# module.net
KiCad netlist of a schematic drawn in EAGLE
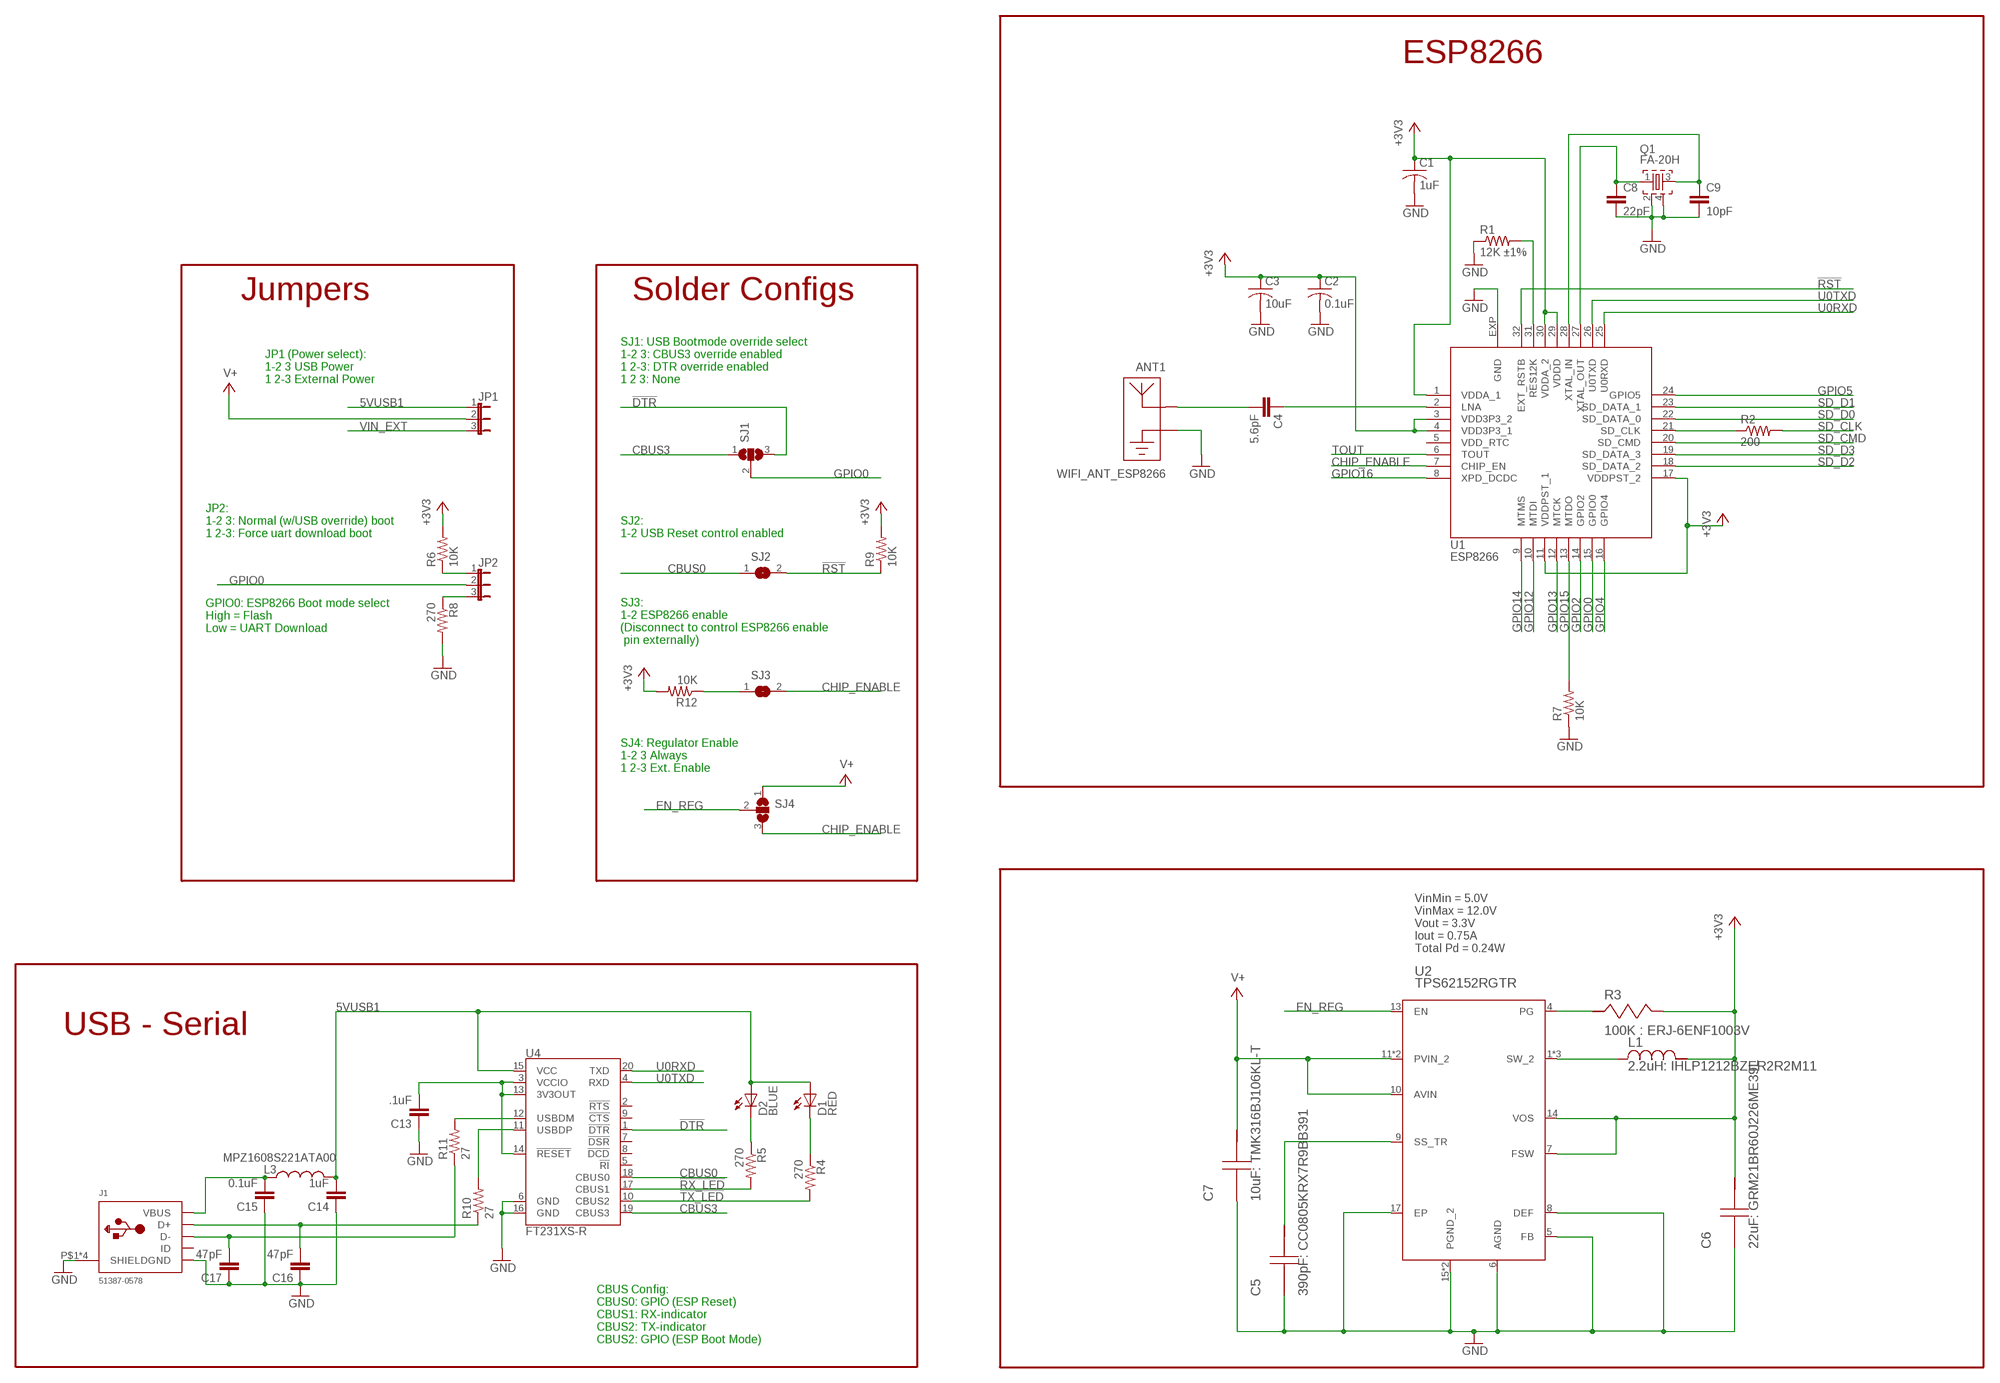
[diagram p0: schematic, sheet 1, part 1 of 2]
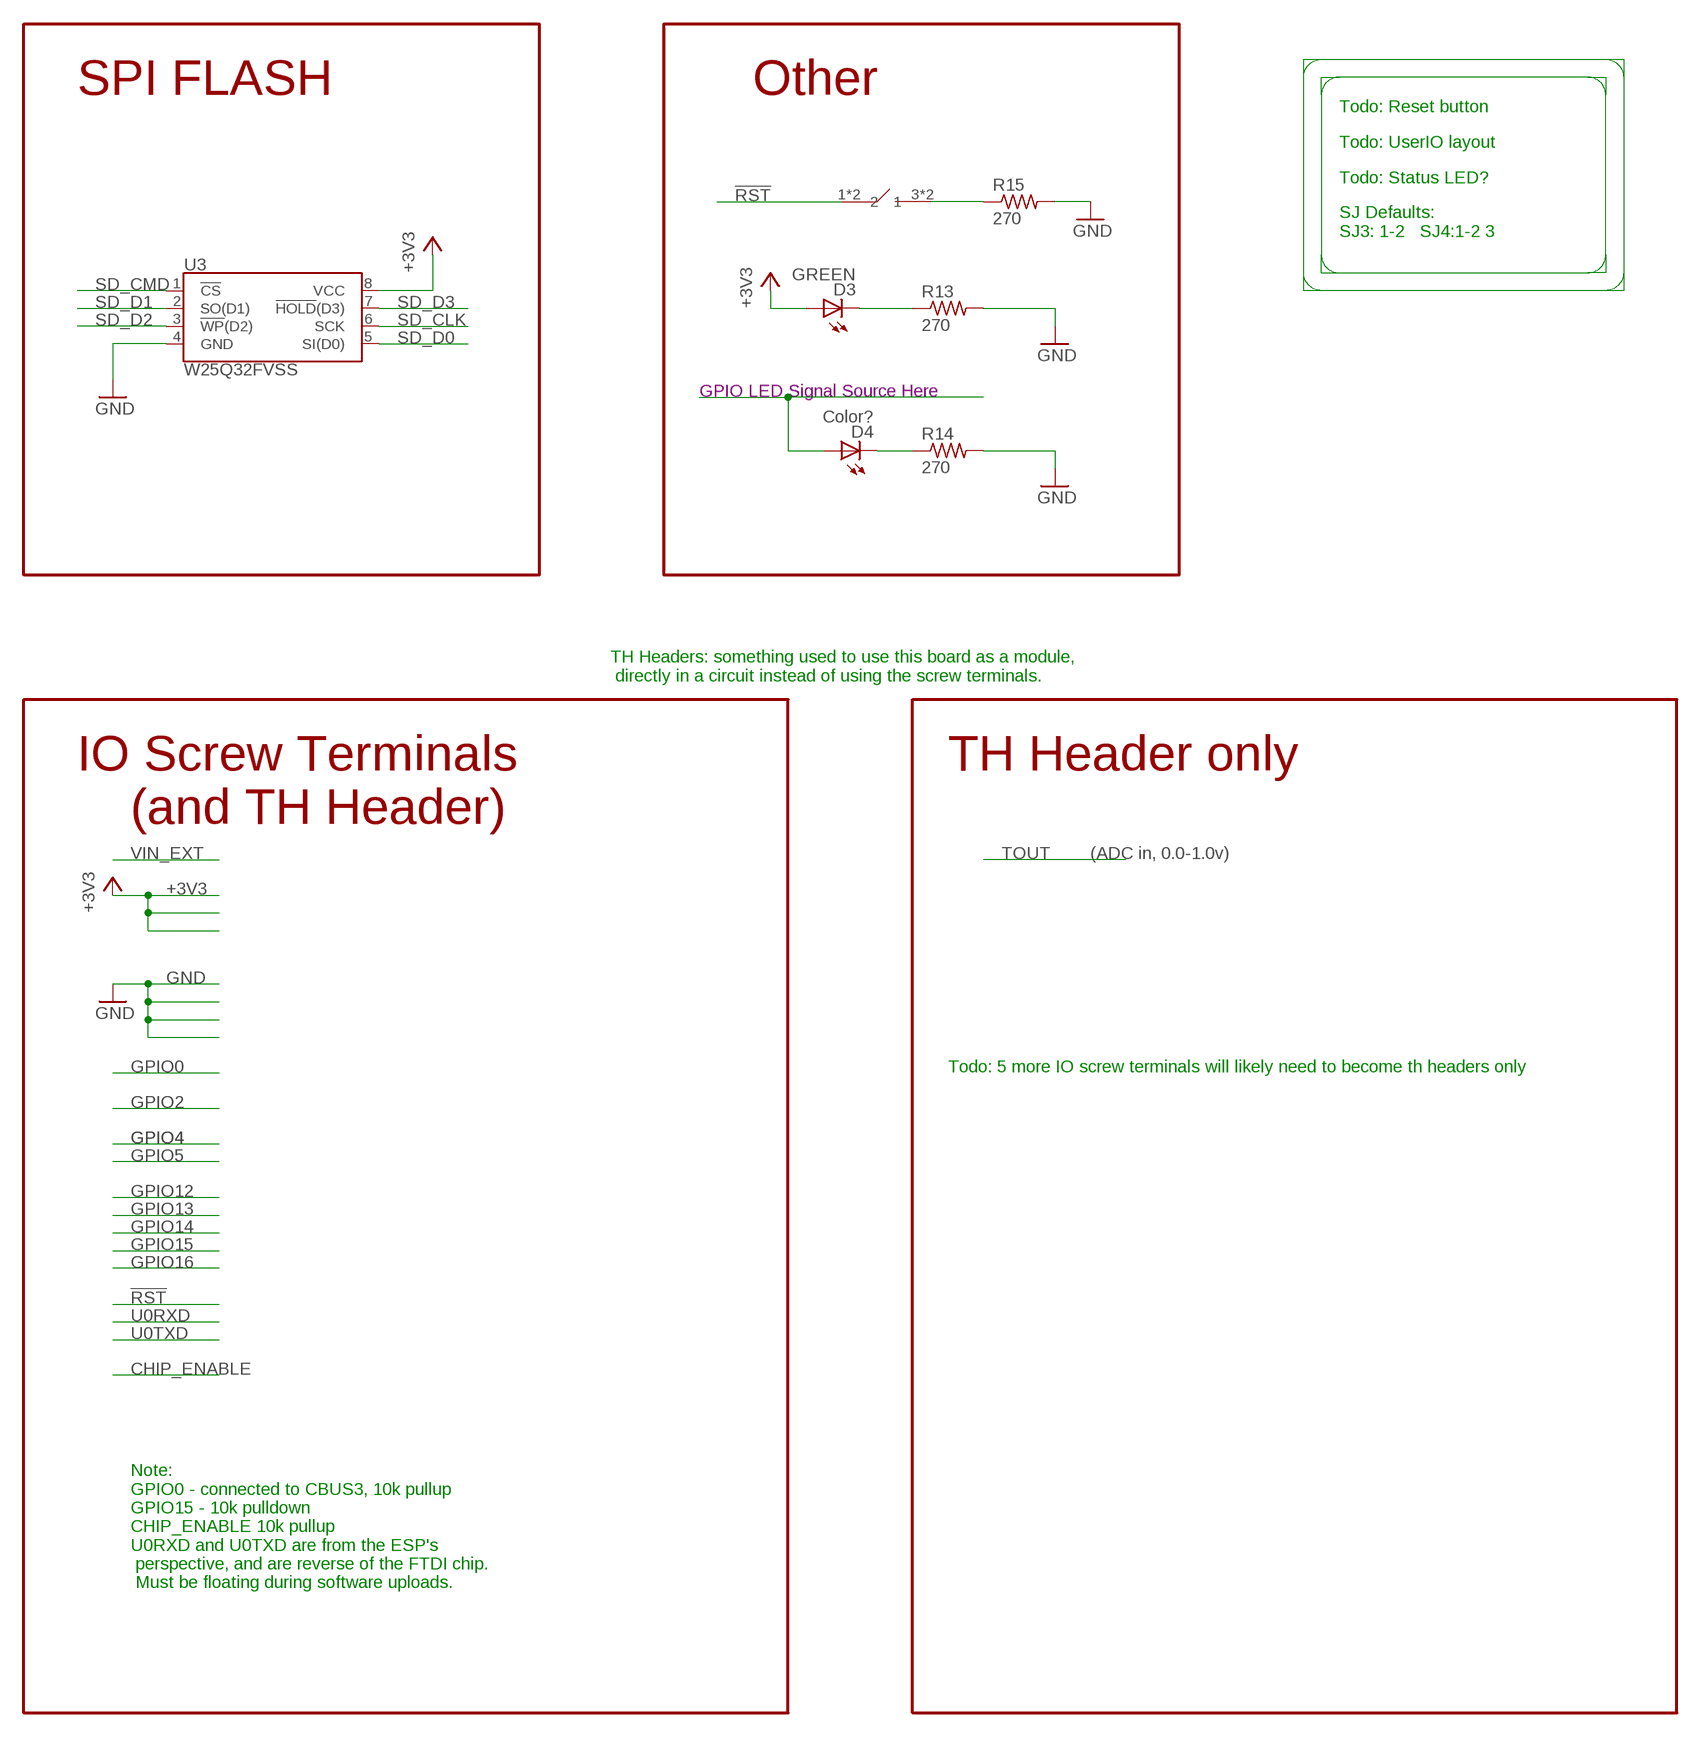
[diagram p1: schematic, sheet 1, part 2 of 2]

(export (version "E")
  (design (tool "Eeschema 10.0.6"))
  (components
    (comp (ref "ANT1")
      (value "WIFI_ANT_ESP8266")
      (footprint "eagle-import:ESP8266_ANT")
      (libsource (lib "eagle-import") (part "WIFI_ANT_ESP8266"))
    )
    (comp (ref "C1")
      (value "1uF")
      (footprint "eagle-import:C0603")
      (libsource (lib "eagle-import") (part "C-USC0603"))
    )
    (comp (ref "C2")
      (value "0.1uF")
      (footprint "eagle-import:C0603")
      (libsource (lib "eagle-import") (part "C-USC0603"))
    )
    (comp (ref "C3")
      (value "10uF")
      (footprint "eagle-import:C0805")
      (libsource (lib "eagle-import") (part "C-USC0805"))
    )
    (comp (ref "C4")
      (value "5.6pF")
      (footprint "eagle-import:C0603")
      (libsource (lib "eagle-import") (part "C-EUC0603"))
    )
    (comp (ref "C5")
      (value "390pF: CC0805KRX7R9BB391")
      (footprint "eagle-import:0805")
      (fields (field (name "MANUFACTURER_PART_NUMBER") "CC0805KRX7R9BB391"))
      (libsource (lib "eagle-import") (part "CC0805KRX7R9BB391"))
    )
    (comp (ref "C6")
      (value "22uF: GRM21BR60J226ME39L")
      (footprint "eagle-import:0805")
      (fields (field (name "MANUFACTURER_PART_NUMBER") "GRM21BR60J226ME39L"))
      (libsource (lib "eagle-import") (part "GRM21BR60J226ME39L"))
    )
    (comp (ref "C7")
      (value "10uF: TMK316BJ106KL-T")
      (footprint "eagle-import:1206")
      (fields (field (name "MANUFACTURER_PART_NUMBER") "TMK316BJ106KL-T"))
      (libsource (lib "eagle-import") (part "TMK316BJ106KL-T"))
    )
    (comp (ref "C8")
      (value "22pF")
      (footprint "eagle-import:C0603")
      (libsource (lib "eagle-import") (part "C-EUC0603"))
    )
    (comp (ref "C9")
      (value "10pF")
      (footprint "eagle-import:C0603")
      (libsource (lib "eagle-import") (part "C-EUC0603"))
    )
    (comp (ref "C13")
      (value ".1uF")
      (footprint "eagle-import:C0603K")
      (libsource (lib "eagle-import") (part "resistor_C-EUC0603K"))
    )
    (comp (ref "C14")
      (value "1uF")
      (footprint "eagle-import:C0603K")
      (libsource (lib "eagle-import") (part "resistor_C-EUC0603K"))
    )
    (comp (ref "C15")
      (value "0.1uF")
      (footprint "eagle-import:C0603K")
      (libsource (lib "eagle-import") (part "resistor_C-EUC0603K"))
    )
    (comp (ref "C16")
      (value "47pF")
      (footprint "eagle-import:C0603K")
      (libsource (lib "eagle-import") (part "resistor_C-EUC0603K"))
    )
    (comp (ref "C17")
      (value "47pF")
      (footprint "eagle-import:C0603K")
      (libsource (lib "eagle-import") (part "resistor_C-EUC0603K"))
    )
    (comp (ref "D1")
      (value "RED")
      (footprint "eagle-import:CHIPLED_0603")
      (libsource (lib "eagle-import") (part "LEDCHIPLED_0603"))
    )
    (comp (ref "D2")
      (value "BLUE")
      (footprint "eagle-import:CHIPLED_0603")
      (libsource (lib "eagle-import") (part "LEDCHIPLED_0603"))
    )
    (comp (ref "D3")
      (value "GREEN")
      (footprint "eagle-import:CHIPLED_0603")
      (libsource (lib "eagle-import") (part "LEDCHIPLED_0603"))
    )
    (comp (ref "D4")
      (value "Color?")
      (footprint "eagle-import:CHIPLED_0603")
      (libsource (lib "eagle-import") (part "LEDCHIPLED_0603"))
    )
    (comp (ref "J1")
      (value "51387-0578")
      (footprint "eagle-import:USB-MINIB-0513870578")
      (libsource (lib "eagle-import") (part "USB"))
    )
    (comp (ref "JP1")
      (value "JP2E")
      (footprint "eagle-import:JP2")
      (libsource (lib "eagle-import") (part "JP2E"))
    )
    (comp (ref "JP2")
      (value "JP2E")
      (footprint "eagle-import:JP2")
      (libsource (lib "eagle-import") (part "JP2E"))
    )
    (comp (ref "L1")
      (value "2.2uH: IHLP1212BZER2R2M11")
      (footprint "eagle-import:IHLP-1212BZ")
      (fields
        (field (name "MANUFACTURER") "Vishay")
        (field (name "MANUFACTURER_PART_NUMBER") "IHLP1212BZER2R2M11")
      )
      (libsource (lib "eagle-import") (part "IHLP1212BZER2R2M11"))
    )
    (comp (ref "L3")
      (value "MPZ1608S221ATA00")
      (footprint "eagle-import:0603")
      (libsource (lib "eagle-import") (part "INDUCTOR0603"))
    )
    (comp (ref "Q1")
      (value "FA-20H")
      (footprint "eagle-import:FA-20H")
      (libsource (lib "eagle-import") (part "FA-20H"))
    )
    (comp (ref "R1")
      (value "12K ±1%")
      (footprint "eagle-import:R0603")
      (libsource (lib "eagle-import") (part "R-US_R0603"))
    )
    (comp (ref "R2")
      (value "200")
      (footprint "eagle-import:R0603")
      (libsource (lib "eagle-import") (part "R-US_R0603"))
    )
    (comp (ref "R3")
      (value "100K : ERJ-6ENF1003V")
      (footprint "eagle-import:0805")
      (fields
        (field (name "MANUFACTURER_PART_NUMBER") "ERJ-6ENF1003V")
        (field (name "POWER") "0.125")
        (field (name "TOLERANCE") "1.0")
      )
      (libsource (lib "eagle-import") (part "ERJ-6ENF1003V"))
    )
    (comp (ref "R4")
      (value "270")
      (footprint "eagle-import:R0603")
      (libsource (lib "eagle-import") (part "resistor_R-US_R0603"))
    )
    (comp (ref "R5")
      (value "270")
      (footprint "eagle-import:R0603")
      (libsource (lib "eagle-import") (part "resistor_R-US_R0603"))
    )
    (comp (ref "R6")
      (value "10K")
      (footprint "eagle-import:R0603")
      (libsource (lib "eagle-import") (part "R-US_R0603"))
    )
    (comp (ref "R7")
      (value "10K")
      (footprint "eagle-import:R0603")
      (libsource (lib "eagle-import") (part "R-US_R0603"))
    )
    (comp (ref "R8")
      (value "270")
      (footprint "eagle-import:R0603")
      (libsource (lib "eagle-import") (part "resistor_R-US_R0603"))
    )
    (comp (ref "R9")
      (value "10K")
      (footprint "eagle-import:R0603")
      (libsource (lib "eagle-import") (part "R-US_R0603"))
    )
    (comp (ref "R10")
      (value "27")
      (footprint "eagle-import:R0603")
      (libsource (lib "eagle-import") (part "resistor_R-US_R0603"))
    )
    (comp (ref "R11")
      (value "27")
      (footprint "eagle-import:R0603")
      (libsource (lib "eagle-import") (part "resistor_R-US_R0603"))
    )
    (comp (ref "R12")
      (value "10K")
      (footprint "eagle-import:R0603")
      (libsource (lib "eagle-import") (part "R-US_R0603"))
    )
    (comp (ref "R13")
      (value "270")
      (footprint "eagle-import:R0603")
      (libsource (lib "eagle-import") (part "resistor_R-US_R0603"))
    )
    (comp (ref "R14")
      (value "270")
      (footprint "eagle-import:R0603")
      (libsource (lib "eagle-import") (part "resistor_R-US_R0603"))
    )
    (comp (ref "R15")
      (value "270")
      (footprint "eagle-import:R0603")
      (libsource (lib "eagle-import") (part "resistor_R-US_R0603"))
    )
    (comp (ref "SJ1")
      (value "SJ2W")
      (footprint "eagle-import:SJ_2")
      (libsource (lib "eagle-import") (part "SJ2W"))
    )
    (comp (ref "SJ2") (value "SJ") (footprint "eagle-import:SJ") (libsource (lib "eagle-import") (part "SJ")))
    (comp (ref "SJ3") (value "SJ") (footprint "eagle-import:SJ") (libsource (lib "eagle-import") (part "SJ")))
    (comp (ref "SJ4")
      (value "SJ2W")
      (footprint "eagle-import:SJ_2")
      (libsource (lib "eagle-import") (part "SJ2W"))
    )
    (comp (ref "U$1")
      (value "PTS645SM43SMTR92DEFAULT")
      (footprint "eagle-import:PTS645SM43SMTR92")
      (libsource (lib "eagle-import") (part "PTS645SM43SMTR92DEFAULT"))
    )
    (comp (ref "U1")
      (value "ESP8266")
      (footprint "eagle-import:HVQFN32")
      (libsource (lib "eagle-import") (part "ESP8266"))
    )
    (comp (ref "U2")
      (value "TPS62152RGTR")
      (footprint "eagle-import:S-PVQFN-N16")
      (fields (field (name "MANUFACTURER_PART_NUMBER") "TPS62131RGTR"))
      (libsource (lib "eagle-import") (part "TPS62152RGTR"))
    )
    (comp (ref "U3")
      (value "W25Q32FVSS")
      (footprint "eagle-import:SOIC-8")
      (libsource (lib "eagle-import") (part "W25Q32FVSS"))
    )
    (comp (ref "U4")
      (value "FT231XS-R")
      (footprint "eagle-import:SSOP20_L")
      (libsource (lib "eagle-import") (part "FT231XS"))
    )
  )
  (nets
    (net (code "1") (name "+3V3") (class "Default")
      (node (ref "C1") (pin "1") (pinfunction "1_1") (pintype "passive"))
      (node (ref "C2") (pin "1") (pinfunction "1_1") (pintype "passive"))
      (node (ref "C3") (pin "1") (pinfunction "1_1") (pintype "passive"))
      (node (ref "C6") (pin "1") (pinfunction "1_1") (pintype "passive"))
      (node (ref "D3") (pin "A") (pinfunction "A_A") (pintype "passive"))
      (node (ref "L1") (pin "2") (pinfunction "2_2") (pintype "passive"))
      (node (ref "R12") (pin "2") (pinfunction "2_2") (pintype "passive"))
      (node (ref "R3") (pin "1") (pinfunction "1_1") (pintype "passive"))
      (node (ref "R6") (pin "2") (pinfunction "2_2") (pintype "passive"))
      (node (ref "R9") (pin "2") (pinfunction "2_2") (pintype "passive"))
      (node (ref "U1") (pin "1") (pinfunction "VDDA_1_1") (pintype "bidirectional"))
      (node (ref "U1") (pin "11") (pinfunction "VDDPST_1_11") (pintype "bidirectional"))
      (node (ref "U1") (pin "17") (pinfunction "VDDPST_2_17") (pintype "bidirectional"))
      (node (ref "U1") (pin "29") (pinfunction "VDDD_29") (pintype "bidirectional"))
      (node (ref "U1") (pin "3") (pinfunction "VDD3P3_2_3") (pintype "bidirectional"))
      (node (ref "U1") (pin "30") (pinfunction "VDDA_2_30") (pintype "bidirectional"))
      (node (ref "U1") (pin "4") (pinfunction "VDD3P3_1_4") (pintype "bidirectional"))
      (node (ref "U2") (pin "14") (pinfunction "VOS_14") (pintype "passive"))
      (node (ref "U2") (pin "7") (pinfunction "FSW_7") (pintype "passive"))
      (node (ref "U3") (pin "8") (pinfunction "VCC_8") (pintype "bidirectional"))
    )
    (net (code "2") (name "/5VUSB1") (class "Default")
      (node (ref "C14") (pin "2") (pinfunction "2_2") (pintype "passive"))
      (node (ref "D1") (pin "A") (pinfunction "A_A") (pintype "passive"))
      (node (ref "D2") (pin "A") (pinfunction "A_A") (pintype "passive"))
      (node (ref "JP1") (pin "1") (pinfunction "1_1") (pintype "passive"))
      (node (ref "L3") (pin "2") (pinfunction "2_2") (pintype "passive"))
      (node (ref "U4") (pin "15") (pinfunction "VCC_15") (pintype "bidirectional"))
    )
    (net (code "3") (name "/CBUS0") (class "Default")
      (node (ref "SJ2") (pin "1") (pinfunction "1_1") (pintype "passive"))
      (node (ref "U4") (pin "18") (pinfunction "CBUS0_18") (pintype "bidirectional"))
    )
    (net (code "4") (name "/CBUS3") (class "Default")
      (node (ref "SJ1") (pin "1") (pinfunction "1_1") (pintype "passive"))
      (node (ref "U4") (pin "19") (pinfunction "CBUS3_19") (pintype "bidirectional"))
    )
    (net (code "5") (name "/CHIP_ENABLE") (class "Default")
      (node (ref "SJ3") (pin "2") (pinfunction "2_2") (pintype "passive"))
      (node (ref "SJ4") (pin "3") (pinfunction "3_3") (pintype "passive"))
      (node (ref "U1") (pin "7") (pinfunction "CHIP_EN_7") (pintype "bidirectional"))
    )
    (net (code "6") (name "/EN_REG") (class "Default")
      (node (ref "SJ4") (pin "2") (pinfunction "2_2") (pintype "passive"))
      (node (ref "U2") (pin "13") (pinfunction "EN_13") (pintype "passive"))
    )
    (net (code "7") (name "/GPIO0") (class "Default")
      (node (ref "JP2") (pin "2") (pinfunction "2_2") (pintype "passive"))
      (node (ref "SJ1") (pin "2") (pinfunction "2_2") (pintype "passive"))
      (node (ref "U1") (pin "15") (pinfunction "GPIO0_15") (pintype "bidirectional"))
    )
    (net (code "8") (name "/GPIO2") (class "Default")
      (node (ref "U1") (pin "14") (pinfunction "GPIO2_14") (pintype "bidirectional"))
    )
    (net (code "9") (name "/GPIO4") (class "Default")
      (node (ref "U1") (pin "16") (pinfunction "GPIO4_16") (pintype "bidirectional"))
    )
    (net (code "10") (name "/GPIO5") (class "Default")
      (node (ref "U1") (pin "24") (pinfunction "GPIO5_24") (pintype "bidirectional"))
    )
    (net (code "11") (name "/GPIO12") (class "Default")
      (node (ref "U1") (pin "10") (pinfunction "MTDI_10") (pintype "bidirectional"))
    )
    (net (code "12") (name "/GPIO13") (class "Default")
      (node (ref "U1") (pin "12") (pinfunction "MTCK_12") (pintype "bidirectional"))
    )
    (net (code "13") (name "/GPIO14") (class "Default")
      (node (ref "U1") (pin "9") (pinfunction "MTMS_9") (pintype "bidirectional"))
    )
    (net (code "14") (name "/GPIO15") (class "Default")
      (node (ref "R7") (pin "2") (pinfunction "2_2") (pintype "passive"))
      (node (ref "U1") (pin "13") (pinfunction "MTDO_13") (pintype "bidirectional"))
    )
    (net (code "15") (name "/GPIO16") (class "Default")
      (node (ref "U1") (pin "8") (pinfunction "XPD_DCDC_8") (pintype "bidirectional"))
    )
    (net (code "16") (name "/SD_CLK") (class "Default")
      (node (ref "R2") (pin "2") (pinfunction "2_2") (pintype "passive"))
      (node (ref "U3") (pin "6") (pinfunction "SCK_6") (pintype "bidirectional"))
    )
    (net (code "17") (name "/SD_CMD") (class "Default")
      (node (ref "U1") (pin "20") (pinfunction "SD_CMD_20") (pintype "bidirectional"))
      (node (ref "U3") (pin "1") (pinfunction "~{CS}_1") (pintype "bidirectional"))
    )
    (net (code "18") (name "/SD_D0") (class "Default")
      (node (ref "U1") (pin "22") (pinfunction "SD_DATA_0_22") (pintype "bidirectional"))
      (node (ref "U3") (pin "5") (pinfunction "SI(D0)_5") (pintype "bidirectional"))
    )
    (net (code "19") (name "/SD_D1") (class "Default")
      (node (ref "U1") (pin "23") (pinfunction "SD_DATA_1_23") (pintype "bidirectional"))
      (node (ref "U3") (pin "2") (pinfunction "SO(D1)_2") (pintype "bidirectional"))
    )
    (net (code "20") (name "/SD_D2") (class "Default")
      (node (ref "U1") (pin "18") (pinfunction "SD_DATA_2_18") (pintype "bidirectional"))
      (node (ref "U3") (pin "3") (pinfunction "~{WP}(D2)_3") (pintype "bidirectional"))
    )
    (net (code "21") (name "/SD_D3") (class "Default")
      (node (ref "U1") (pin "19") (pinfunction "SD_DATA_3_19") (pintype "bidirectional"))
      (node (ref "U3") (pin "7") (pinfunction "~{HOLD}(D3)_7") (pintype "bidirectional"))
    )
    (net (code "22") (name "/TOUT") (class "Default")
      (node (ref "U1") (pin "6") (pinfunction "TOUT_6") (pintype "bidirectional"))
    )
    (net (code "23") (name "/U0RXD") (class "Default")
      (node (ref "U1") (pin "25") (pinfunction "U0RXD_25") (pintype "bidirectional"))
      (node (ref "U4") (pin "20") (pinfunction "TXD_20") (pintype "bidirectional"))
    )
    (net (code "24") (name "/U0TXD") (class "Default")
      (node (ref "U1") (pin "26") (pinfunction "U0TXD_26") (pintype "bidirectional"))
      (node (ref "U4") (pin "4") (pinfunction "RXD_4") (pintype "bidirectional"))
    )
    (net (code "25") (name "/VIN_EXT") (class "Default")
      (node (ref "JP1") (pin "3") (pinfunction "3_3") (pintype "passive"))
    )
    (net (code "26") (name "/~{DTR}") (class "Default")
      (node (ref "SJ1") (pin "3") (pinfunction "3_3") (pintype "passive"))
      (node (ref "U4") (pin "1") (pinfunction "~{DTR}_1") (pintype "bidirectional"))
    )
    (net (code "27") (name "/~{RST}") (class "Default")
      (node (ref "R9") (pin "1") (pinfunction "1_1") (pintype "passive"))
      (node (ref "SJ2") (pin "2") (pinfunction "2_2") (pintype "passive"))
      (node (ref "U$1") (pin "1") (pinfunction "1_1") (pintype "bidirectional"))
      (node (ref "U$1") (pin "2") (pinfunction "1_2") (pintype "bidirectional"))
      (node (ref "U1") (pin "32") (pinfunction "EXT_RSTB_32") (pintype "bidirectional"))
    )
    (net (code "28") (name "/~{RX_LED}") (class "Default")
      (node (ref "R5") (pin "2") (pinfunction "2_2") (pintype "passive"))
      (node (ref "U4") (pin "17") (pinfunction "CBUS1_17") (pintype "bidirectional"))
    )
    (net (code "29") (name "/~{TX_LED}") (class "Default")
      (node (ref "R4") (pin "2") (pinfunction "2_2") (pintype "passive"))
      (node (ref "U4") (pin "10") (pinfunction "CBUS2_10") (pintype "bidirectional"))
    )
    (net (code "30") (name "GND") (class "Default")
      (node (ref "ANT1") (pin "GND") (pinfunction "GND_GND") (pintype "input"))
      (node (ref "C1") (pin "2") (pinfunction "2_2") (pintype "passive"))
      (node (ref "C13") (pin "1") (pinfunction "1_1") (pintype "passive"))
      (node (ref "C14") (pin "1") (pinfunction "1_1") (pintype "passive"))
      (node (ref "C15") (pin "1") (pinfunction "1_1") (pintype "passive"))
      (node (ref "C16") (pin "1") (pinfunction "1_1") (pintype "passive"))
      (node (ref "C17") (pin "1") (pinfunction "1_1") (pintype "passive"))
      (node (ref "C2") (pin "2") (pinfunction "2_2") (pintype "passive"))
      (node (ref "C3") (pin "2") (pinfunction "2_2") (pintype "passive"))
      (node (ref "C5") (pin "2") (pinfunction "2_2") (pintype "passive"))
      (node (ref "C6") (pin "2") (pinfunction "2_2") (pintype "passive"))
      (node (ref "C7") (pin "2") (pinfunction "2_2") (pintype "passive"))
      (node (ref "C8") (pin "2") (pinfunction "2_2") (pintype "passive"))
      (node (ref "C9") (pin "2") (pinfunction "2_2") (pintype "passive"))
      (node (ref "J1") (pin "GND") (pinfunction "GND_GND") (pintype "power_in"))
      (node (ref "J1") (pin "P$1") (pinfunction "SHIELD_P$1") (pintype "bidirectional"))
      (node (ref "J1") (pin "P$2") (pinfunction "SHIELD_P$2") (pintype "bidirectional"))
      (node (ref "J1") (pin "P$3") (pinfunction "SHIELD_P$3") (pintype "bidirectional"))
      (node (ref "J1") (pin "P$4") (pinfunction "SHIELD_P$4") (pintype "bidirectional"))
      (node (ref "Q1") (pin "2") (pinfunction "2_2") (pintype "passive"))
      (node (ref "Q1") (pin "4") (pinfunction "4_4") (pintype "passive"))
      (node (ref "R1") (pin "1") (pinfunction "1_1") (pintype "passive"))
      (node (ref "R13") (pin "2") (pinfunction "2_2") (pintype "passive"))
      (node (ref "R14") (pin "2") (pinfunction "2_2") (pintype "passive"))
      (node (ref "R15") (pin "2") (pinfunction "2_2") (pintype "passive"))
      (node (ref "R7") (pin "1") (pinfunction "1_1") (pintype "passive"))
      (node (ref "R8") (pin "2") (pinfunction "2_2") (pintype "passive"))
      (node (ref "U1") (pin "EXP") (pinfunction "GND_EXP") (pintype "bidirectional"))
      (node (ref "U2") (pin "15") (pinfunction "PGND_2_15") (pintype "passive"))
      (node (ref "U2") (pin "16") (pinfunction "PGND_2_16") (pintype "passive"))
      (node (ref "U2") (pin "17") (pinfunction "EP_17") (pintype "passive"))
      (node (ref "U2") (pin "5") (pinfunction "FB_5") (pintype "passive"))
      (node (ref "U2") (pin "6") (pinfunction "AGND_6") (pintype "passive"))
      (node (ref "U2") (pin "8") (pinfunction "DEF_8") (pintype "passive"))
      (node (ref "U3") (pin "4") (pinfunction "GND_4") (pintype "bidirectional"))
      (node (ref "U4") (pin "16") (pinfunction "GND_16") (pintype "bidirectional"))
      (node (ref "U4") (pin "6") (pinfunction "GND_6") (pintype "bidirectional"))
    )
    (net (code "31") (name "Net-(ANT1-PadANT)") (class "Default")
      (node (ref "ANT1") (pin "ANT") (pinfunction "ANT_ANT") (pintype "input"))
      (node (ref "C4") (pin "2") (pinfunction "2_2") (pintype "passive"))
    )
    (net (code "32") (name "Net-(C15-Pad2)") (class "Default")
      (node (ref "C15") (pin "2") (pinfunction "2_2") (pintype "passive"))
      (node (ref "J1") (pin "VBUS") (pinfunction "VBUS_VBUS") (pintype "power_in"))
      (node (ref "L3") (pin "1") (pinfunction "1_1") (pintype "passive"))
    )
    (net (code "33") (name "Net-(C16-Pad2)") (class "Default")
      (node (ref "C16") (pin "2") (pinfunction "2_2") (pintype "passive"))
      (node (ref "J1") (pin "D+") (pinfunction "D+_D+") (pintype "bidirectional"))
      (node (ref "R10") (pin "1") (pinfunction "1_1") (pintype "passive"))
    )
    (net (code "34") (name "Net-(C17-Pad2)") (class "Default")
      (node (ref "C17") (pin "2") (pinfunction "2_2") (pintype "passive"))
      (node (ref "J1") (pin "D-") (pinfunction "D-_D-") (pintype "bidirectional"))
      (node (ref "R11") (pin "1") (pinfunction "1_1") (pintype "passive"))
    )
    (net (code "35") (name "Net-(D1-PadC)") (class "Default")
      (node (ref "D1") (pin "C") (pinfunction "C_C") (pintype "passive"))
      (node (ref "R4") (pin "1") (pinfunction "1_1") (pintype "passive"))
    )
    (net (code "36") (name "Net-(D2-PadC)") (class "Default")
      (node (ref "D2") (pin "C") (pinfunction "C_C") (pintype "passive"))
      (node (ref "R5") (pin "1") (pinfunction "1_1") (pintype "passive"))
    )
    (net (code "37") (name "Net-(D3-PadC)") (class "Default")
      (node (ref "D3") (pin "C") (pinfunction "C_C") (pintype "passive"))
      (node (ref "R13") (pin "1") (pinfunction "1_1") (pintype "passive"))
    )
    (net (code "38") (name "Net-(D4-PadC)") (class "Default")
      (node (ref "D4") (pin "C") (pinfunction "C_C") (pintype "passive"))
      (node (ref "R14") (pin "1") (pinfunction "1_1") (pintype "passive"))
    )
    (net (code "39") (name "Net-(JP2-Pad1)") (class "Default")
      (node (ref "JP2") (pin "1") (pinfunction "1_1") (pintype "passive"))
      (node (ref "R6") (pin "1") (pinfunction "1_1") (pintype "passive"))
    )
    (net (code "40") (name "Net-(JP2-Pad3)") (class "Default")
      (node (ref "JP2") (pin "3") (pinfunction "3_3") (pintype "passive"))
      (node (ref "R8") (pin "1") (pinfunction "1_1") (pintype "passive"))
    )
    (net (code "41") (name "Net-(L1-Pad1)") (class "Default")
      (node (ref "L1") (pin "1") (pinfunction "1_1") (pintype "passive"))
      (node (ref "U2") (pin "1") (pinfunction "SW_2_1") (pintype "passive"))
      (node (ref "U2") (pin "2") (pinfunction "SW_2_2") (pintype "passive"))
      (node (ref "U2") (pin "3") (pinfunction "SW_2_3") (pintype "passive"))
    )
    (net (code "42") (name "Net-(R12-Pad1)") (class "Default")
      (node (ref "R12") (pin "1") (pinfunction "1_1") (pintype "passive"))
      (node (ref "SJ3") (pin "1") (pinfunction "1_1") (pintype "passive"))
    )
    (net (code "43") (name "Net-(R15-Pad1)") (class "Default")
      (node (ref "R15") (pin "1") (pinfunction "1_1") (pintype "passive"))
      (node (ref "U$1") (pin "3") (pinfunction "2_3") (pintype "bidirectional"))
      (node (ref "U$1") (pin "4") (pinfunction "2_4") (pintype "bidirectional"))
    )
    (net (code "44") (name "Net-(U1-LNA)") (class "Default")
      (node (ref "C4") (pin "1") (pinfunction "1_1") (pintype "passive"))
      (node (ref "U1") (pin "2") (pinfunction "LNA_2") (pintype "bidirectional"))
    )
    (net (code "45") (name "Net-(U1-RES12K)") (class "Default")
      (node (ref "R1") (pin "2") (pinfunction "2_2") (pintype "passive"))
      (node (ref "U1") (pin "31") (pinfunction "RES12K_31") (pintype "bidirectional"))
    )
    (net (code "46") (name "Net-(U1-SD_CLK)") (class "Default")
      (node (ref "R2") (pin "1") (pinfunction "1_1") (pintype "passive"))
      (node (ref "U1") (pin "21") (pinfunction "SD_CLK_21") (pintype "bidirectional"))
    )
    (net (code "47") (name "Net-(U1-XTAL_IN)") (class "Default")
      (node (ref "C9") (pin "1") (pinfunction "1_1") (pintype "passive"))
      (node (ref "Q1") (pin "3") (pinfunction "3_3") (pintype "passive"))
      (node (ref "U1") (pin "28") (pinfunction "XTAL_IN_28") (pintype "bidirectional"))
    )
    (net (code "48") (name "Net-(U1-XTAL_OUT)") (class "Default")
      (node (ref "C8") (pin "1") (pinfunction "1_1") (pintype "passive"))
      (node (ref "Q1") (pin "1") (pinfunction "1_1") (pintype "passive"))
      (node (ref "U1") (pin "27") (pinfunction "XTAL_OUT_27") (pintype "bidirectional"))
    )
    (net (code "49") (name "Net-(U2-PG)") (class "Default")
      (node (ref "R3") (pin "2") (pinfunction "2_2") (pintype "passive"))
      (node (ref "U2") (pin "4") (pinfunction "PG_4") (pintype "passive"))
    )
    (net (code "50") (name "Net-(U2-SS_TR)") (class "Default")
      (node (ref "C5") (pin "1") (pinfunction "1_1") (pintype "passive"))
      (node (ref "U2") (pin "9") (pinfunction "SS_TR_9") (pintype "passive"))
    )
    (net (code "51") (name "Net-(U4-3V3OUT)") (class "Default")
      (node (ref "C13") (pin "2") (pinfunction "2_2") (pintype "passive"))
      (node (ref "U4") (pin "13") (pinfunction "3V3OUT_13") (pintype "bidirectional"))
      (node (ref "U4") (pin "14") (pinfunction "~{RESET}_14") (pintype "bidirectional"))
      (node (ref "U4") (pin "3") (pinfunction "VCCIO_3") (pintype "bidirectional"))
    )
    (net (code "52") (name "Net-(U4-USBDM)") (class "Default")
      (node (ref "R11") (pin "2") (pinfunction "2_2") (pintype "passive"))
      (node (ref "U4") (pin "12") (pinfunction "USBDM_12") (pintype "bidirectional"))
    )
    (net (code "53") (name "Net-(U4-USBDP)") (class "Default")
      (node (ref "R10") (pin "2") (pinfunction "2_2") (pintype "passive"))
      (node (ref "U4") (pin "11") (pinfunction "USBDP_11") (pintype "bidirectional"))
    )
    (net (code "54") (name "V+") (class "Default")
      (node (ref "C7") (pin "1") (pinfunction "1_1") (pintype "passive"))
      (node (ref "JP1") (pin "2") (pinfunction "2_2") (pintype "passive"))
      (node (ref "SJ4") (pin "1") (pinfunction "1_1") (pintype "passive"))
      (node (ref "U2") (pin "10") (pinfunction "AVIN_10") (pintype "passive"))
      (node (ref "U2") (pin "11") (pinfunction "PVIN_2_11") (pintype "passive"))
      (node (ref "U2") (pin "12") (pinfunction "PVIN_2_12") (pintype "passive"))
    )
    (net (code "55") (name "unconnected-(D4-PadA)") (class "Default")
      (node (ref "D4") (pin "A") (pinfunction "A_A") (pintype "passive"))
    )
    (net (code "56") (name "unconnected-(J1-PadID)") (class "Default")
      (node (ref "J1") (pin "ID") (pinfunction "ID_ID") (pintype "bidirectional"))
    )
    (net (code "57") (name "unconnected-(U1-VDD_RTC-Pad5)") (class "Default")
      (node (ref "U1") (pin "5") (pinfunction "VDD_RTC_5") (pintype "bidirectional"))
    )
    (net (code "58") (name "unconnected-(U4-~{CTS}-Pad9)") (class "Default")
      (node (ref "U4") (pin "9") (pinfunction "~{CTS}_9") (pintype "bidirectional"))
    )
    (net (code "59") (name "unconnected-(U4-~{DCD}-Pad8)") (class "Default")
      (node (ref "U4") (pin "8") (pinfunction "~{DCD}_8") (pintype "bidirectional"))
    )
    (net (code "60") (name "unconnected-(U4-~{DSR}-Pad7)") (class "Default")
      (node (ref "U4") (pin "7") (pinfunction "~{DSR}_7") (pintype "bidirectional"))
    )
    (net (code "61") (name "unconnected-(U4-~{RI}-Pad5)") (class "Default")
      (node (ref "U4") (pin "5") (pinfunction "~{RI}_5") (pintype "bidirectional"))
    )
    (net (code "62") (name "unconnected-(U4-~{RTS}-Pad2)") (class "Default")
      (node (ref "U4") (pin "2") (pinfunction "~{RTS}_2") (pintype "bidirectional"))
    )
  )
)
